# Lab10.net
KiCad netlist of a schematic drawn in Altium Designer
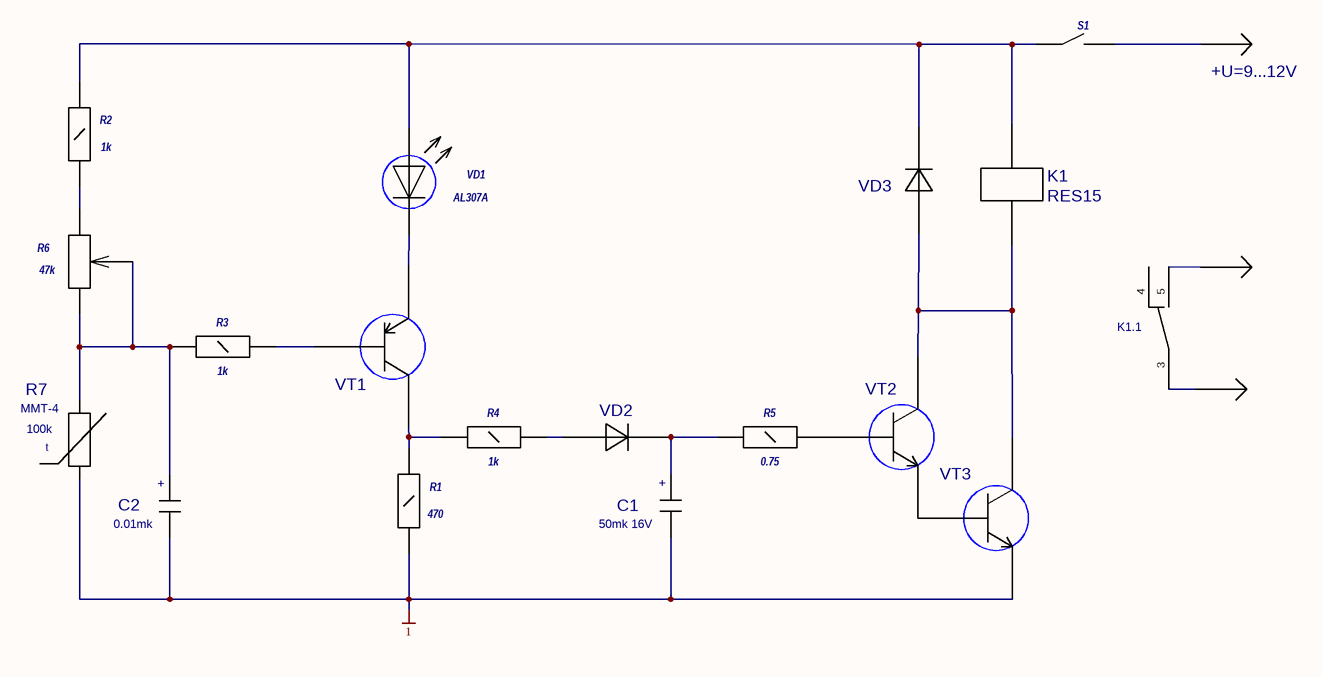
[diagram p0: Lab10.SCHDOC]

(export (version "E")
  (design (tool "Eeschema 10.0.6"))
  (components
    (comp (ref "1")
      (value "+U=9...12V")
      (footprint "XP_1")
      (description "XP_1")
      (libsource (lib "*") (part "XP_1"))
    )
    (comp (ref "2") (value "K1.1") (footprint "K1.1") (libsource (lib "*") (part "K1.1")))
    (comp (ref "3") (value "XP_1") (footprint "XP_1") (libsource (lib "*") (part "XP_1")))
    (comp (ref "4") (value "XP_1") (footprint "XP_1") (libsource (lib "*") (part "XP_1")))
    (comp (ref "C1")
      (value "50mk 16V")
      (footprint "CAP2")
      (description "CAP2")
      (libsource (lib "*") (part "CAP2"))
    )
    (comp (ref "C2")
      (value "0.01mk")
      (footprint "CAP2")
      (description "CAP2")
      (libsource (lib "*") (part "CAP2"))
    )
    (comp (ref "K1") (value "RES15") (footprint "RES15") (libsource (lib "*") (part "RES15")))
    (comp (ref "R1")
      (value "470")
      (footprint "МЛТ(0.25)")
      (description "МЛТ(0.25)")
      (libsource (lib "*") (part "МЛТ(0.25)"))
    )
    (comp (ref "R2")
      (value "1k")
      (footprint "МЛТ(0.25)")
      (description "МЛТ(0.25)")
      (libsource (lib "*") (part "МЛТ(0.25)"))
    )
    (comp (ref "R3")
      (value "1k")
      (footprint "МЛТ(0.25)")
      (description "МЛТ(0.25)")
      (libsource (lib "*") (part "МЛТ(0.25)"))
    )
    (comp (ref "R4")
      (value "1k")
      (footprint "МЛТ(0.25)")
      (description "МЛТ(0.25)")
      (libsource (lib "*") (part "МЛТ(0.25)"))
    )
    (comp (ref "R5")
      (value "0.75")
      (footprint "МЛТ(0.25)")
      (description "МЛТ(0.25)")
      (libsource (lib "*") (part "МЛТ(0.25)"))
    )
    (comp (ref "R6")
      (value "47k")
      (footprint "СП3-38В")
      (description "СП3-38В")
      (libsource (lib "*") (part "СП3-38В"))
    )
    (comp (ref "R7")
      (value "MMT-4")
      (footprint "MMT-4")
      (fields (field (name "ALTIUM_VALUE") "100k"))
      (libsource (lib "*") (part "MMT-4"))
    )
    (comp (ref "S1") (value "T1") (footprint "Т1") (libsource (lib "*") (part "T1")))
    (comp (ref "VD1") (value "AL307A") (footprint "АЛ307") (libsource (lib "*") (part "AL307A")))
    (comp (ref "VD2") (value "КД209") (footprint "DO-7") (libsource (lib "*") (part "КД209")))
    (comp (ref "VD3") (value "КД209") (footprint "DO-7") (libsource (lib "*") (part "КД209")))
    (comp (ref "VT1") (value "КТ361") (footprint "КТ315") (libsource (lib "*") (part "КТ361")))
    (comp (ref "VT2") (value "КТ315") (footprint "КТ315") (libsource (lib "*") (part "КТ315")))
    (comp (ref "VT3") (value "КТ315") (footprint "КТ315") (libsource (lib "") (part "КТ315_1")))
  )
  (nets
    (net (code "1") (name "1") (class "Default")
      (node (ref "C1") (pin "2") (pinfunction "2_2") (pintype "passive"))
      (node (ref "C2") (pin "2") (pinfunction "2_2") (pintype "passive"))
      (node (ref "R1") (pin "1") (pinfunction "1_1") (pintype "passive"))
      (node (ref "R7") (pin "2") (pinfunction "I/O0_2") (pintype "passive"))
      (node (ref "VT3") (pin "3") (pinfunction "A3_3") (pintype "passive"))
    )
    (net (code "2") (name "Net-(1-A1)") (class "Default")
      (node (ref "1") (pin "1") (pinfunction "A1_1") (pintype "passive"))
      (node (ref "S1") (pin "2") (pinfunction "2_2") (pintype "passive"))
    )
    (net (code "3") (name "Net-(3-A1)") (class "Default")
      (node (ref "2") (pin "5") (pinfunction "5_5") (pintype "passive"))
      (node (ref "3") (pin "1") (pinfunction "A1_1") (pintype "passive"))
    )
    (net (code "4") (name "Net-(4-A1)") (class "Default")
      (node (ref "2") (pin "3") (pinfunction "3_3") (pintype "passive"))
      (node (ref "4") (pin "1") (pinfunction "A1_1") (pintype "passive"))
    )
    (net (code "5") (name "Net-(K1-A)") (class "Default")
      (node (ref "K1") (pin "1") (pinfunction "A_1") (pintype "passive"))
      (node (ref "R2") (pin "2") (pinfunction "2_2") (pintype "passive"))
      (node (ref "S1") (pin "1") (pinfunction "1_1") (pintype "passive"))
      (node (ref "VD1") (pin "1") (pinfunction "1_1") (pintype "passive"))
      (node (ref "VD3") (pin "1") (pinfunction "K_1") (pintype "passive"))
    )
    (net (code "6") (name "Net-(K1-B)") (class "Default")
      (node (ref "K1") (pin "2") (pinfunction "B_2") (pintype "passive"))
      (node (ref "VD3") (pin "2") (pinfunction "A_2") (pintype "passive"))
      (node (ref "VT2") (pin "2") (pinfunction "A2_2") (pintype "passive"))
      (node (ref "VT3") (pin "2") (pinfunction "A2_2") (pintype "passive"))
    )
    (net (code "7") (name "Net-(R2-Pad1)") (class "Default")
      (node (ref "R2") (pin "1") (pinfunction "1_1") (pintype "passive"))
      (node (ref "R6") (pin "1") (pinfunction "1_1") (pintype "passive"))
    )
    (net (code "8") (name "Net-(R7-I{slash}O1)") (class "Default")
      (node (ref "C2") (pin "1") (pinfunction "1_1") (pintype "passive"))
      (node (ref "R3") (pin "2") (pinfunction "2_2") (pintype "passive"))
      (node (ref "R6") (pin "2") (pinfunction "2_2") (pintype "passive"))
      (node (ref "R6") (pin "3") (pinfunction "3_3") (pintype "passive"))
      (node (ref "R7") (pin "1") (pinfunction "I/O1_1") (pintype "passive"))
    )
    (net (code "9") (name "Net-(VD2-A)") (class "Default")
      (node (ref "R4") (pin "1") (pinfunction "1_1") (pintype "passive"))
      (node (ref "VD2") (pin "2") (pinfunction "A_2") (pintype "passive"))
    )
    (net (code "10") (name "Net-(VD2-K)") (class "Default")
      (node (ref "C1") (pin "1") (pinfunction "1_1") (pintype "passive"))
      (node (ref "R5") (pin "2") (pinfunction "2_2") (pintype "passive"))
      (node (ref "VD2") (pin "1") (pinfunction "K_1") (pintype "passive"))
    )
    (net (code "11") (name "Net-(VT1-A1)") (class "Default")
      (node (ref "R3") (pin "1") (pinfunction "1_1") (pintype "passive"))
      (node (ref "VT1") (pin "1") (pinfunction "A1_1") (pintype "passive"))
    )
    (net (code "12") (name "Net-(VT1-A2)") (class "Default")
      (node (ref "R1") (pin "2") (pinfunction "2_2") (pintype "passive"))
      (node (ref "R4") (pin "2") (pinfunction "2_2") (pintype "passive"))
      (node (ref "VT1") (pin "2") (pinfunction "A2_2") (pintype "passive"))
    )
    (net (code "13") (name "Net-(VT1-A3)") (class "Default")
      (node (ref "VD1") (pin "2") (pinfunction "2_2") (pintype "passive"))
      (node (ref "VT1") (pin "3") (pinfunction "A3_3") (pintype "passive"))
    )
    (net (code "14") (name "Net-(VT2-A1)") (class "Default")
      (node (ref "R5") (pin "1") (pinfunction "1_1") (pintype "passive"))
      (node (ref "VT2") (pin "1") (pinfunction "A1_1") (pintype "passive"))
    )
    (net (code "15") (name "Net-(VT2-A3)") (class "Default")
      (node (ref "VT2") (pin "3") (pinfunction "A3_3") (pintype "passive"))
      (node (ref "VT3") (pin "1") (pinfunction "A1_1") (pintype "passive"))
    )
    (net (code "16") (name "unconnected-(2-Pad4)") (class "Default")
      (node (ref "2") (pin "4") (pinfunction "4_4") (pintype "passive"))
    )
    (net (code "17") (name "unconnected-(K1-Pad3)") (class "Default")
      (node (ref "K1") (pin "3") (pintype "passive"))
    )
    (net (code "18") (name "unconnected-(K1-Pad4)") (class "Default")
      (node (ref "K1") (pin "4") (pintype "passive"))
    )
    (net (code "19") (name "unconnected-(K1-Pad5)") (class "Default")
      (node (ref "K1") (pin "5") (pintype "passive"))
    )
  )
)
